# Wheelmod_rs485.net
KiCad netlist of a schematic drawn in EAGLE
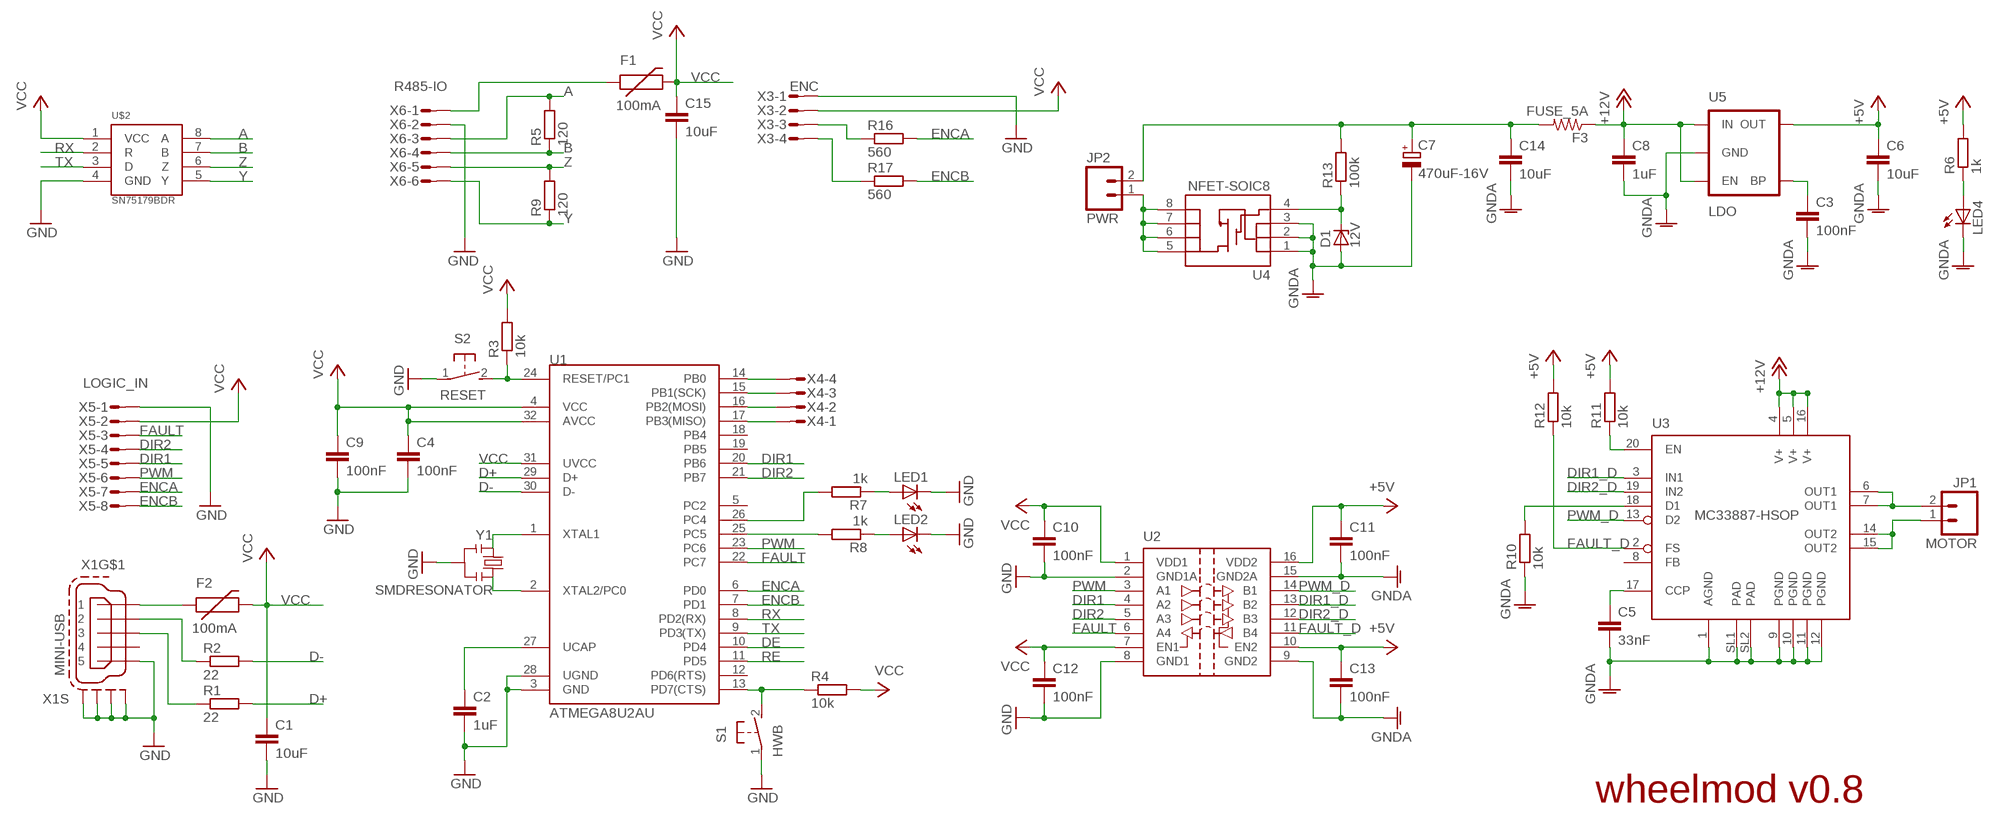
[diagram p0: schematic, sheet 1]

(export (version "E")
  (design (tool "Eeschema 10.0.6"))
  (components
    (comp (ref "C1")
      (value "10uF")
      (footprint "eagle-import:C1206K")
      (libsource (lib "eagle-import") (part "C-EUC1206K"))
    )
    (comp (ref "C2")
      (value "1uF")
      (footprint "eagle-import:C0603K")
      (libsource (lib "eagle-import") (part "C-EUC0603K"))
    )
    (comp (ref "C3")
      (value "100nF")
      (footprint "eagle-import:C0603K")
      (libsource (lib "eagle-import") (part "C-EUC0603K"))
    )
    (comp (ref "C4")
      (value "100nF")
      (footprint "eagle-import:C0603K")
      (libsource (lib "eagle-import") (part "C-EUC0603K"))
    )
    (comp (ref "C5")
      (value "33nF")
      (footprint "eagle-import:C0603K")
      (libsource (lib "eagle-import") (part "C-EUC0603K"))
    )
    (comp (ref "C6")
      (value "10uF")
      (footprint "eagle-import:C1206K")
      (libsource (lib "eagle-import") (part "C-EUC1206K"))
    )
    (comp (ref "C7")
      (value "470uF-16V")
      (footprint "eagle-import:E3,5-8")
      (libsource (lib "eagle-import") (part "CPOL-EUE3.5-8"))
    )
    (comp (ref "C8")
      (value "1uF")
      (footprint "eagle-import:C0603K")
      (libsource (lib "eagle-import") (part "C-EUC0603K"))
    )
    (comp (ref "C9")
      (value "100nF")
      (footprint "eagle-import:C0603K")
      (libsource (lib "eagle-import") (part "C-EUC0603K"))
    )
    (comp (ref "C10")
      (value "100nF")
      (footprint "eagle-import:C0603K")
      (libsource (lib "eagle-import") (part "C-EUC0603K"))
    )
    (comp (ref "C11")
      (value "100nF")
      (footprint "eagle-import:C0603K")
      (libsource (lib "eagle-import") (part "C-EUC0603K"))
    )
    (comp (ref "C12")
      (value "100nF")
      (footprint "eagle-import:C0603K")
      (libsource (lib "eagle-import") (part "C-EUC0603K"))
    )
    (comp (ref "C13")
      (value "100nF")
      (footprint "eagle-import:C0603K")
      (libsource (lib "eagle-import") (part "C-EUC0603K"))
    )
    (comp (ref "C14")
      (value "10uF")
      (footprint "eagle-import:C1206K")
      (libsource (lib "eagle-import") (part "C-EUC1206K"))
    )
    (comp (ref "C15")
      (value "10uF")
      (footprint "eagle-import:C1206K")
      (libsource (lib "eagle-import") (part "C-EUC1206K"))
    )
    (comp (ref "D1")
      (value "12V")
      (footprint "eagle-import:SOD123")
      (libsource (lib "eagle-import") (part "ZENER-DIODESOD123"))
    )
    (comp (ref "F1")
      (value "100mA")
      (footprint "eagle-import:PTC-1206")
      (libsource (lib "eagle-import") (part "PTCSMD"))
    )
    (comp (ref "F2")
      (value "100mA")
      (footprint "eagle-import:PTC-1206")
      (libsource (lib "eagle-import") (part "PTCSMD"))
    )
    (comp (ref "F3")
      (value "FUSE_5A")
      (footprint "eagle-import:R1206")
      (libsource (lib "eagle-import") (part "R-US_R1206"))
    )
    (comp (ref "JP1")
      (value "MOTOR")
      (footprint "eagle-import:SCREWTERMINAL-3.5MM-2")
      (libsource (lib "eagle-import") (part "M023.5MM"))
    )
    (comp (ref "JP2")
      (value "PWR")
      (footprint "eagle-import:SCREWTERMINAL-3.5MM-2")
      (libsource (lib "eagle-import") (part "M023.5MM"))
    )
    (comp (ref "LED1")
      (value "LEDCHIP-LED0603")
      (footprint "eagle-import:CHIP-LED0603")
      (libsource (lib "eagle-import") (part "LEDCHIP-LED0603"))
    )
    (comp (ref "LED2")
      (value "LEDCHIP-LED0603")
      (footprint "eagle-import:CHIP-LED0603")
      (libsource (lib "eagle-import") (part "LEDCHIP-LED0603"))
    )
    (comp (ref "LED4")
      (value "LEDCHIP-LED0603")
      (footprint "eagle-import:CHIP-LED0603")
      (libsource (lib "eagle-import") (part "LEDCHIP-LED0603"))
    )
    (comp (ref "R1")
      (value "22")
      (footprint "eagle-import:R0603")
      (libsource (lib "eagle-import") (part "R-EU_R0603"))
    )
    (comp (ref "R2")
      (value "22")
      (footprint "eagle-import:R0603")
      (libsource (lib "eagle-import") (part "R-EU_R0603"))
    )
    (comp (ref "R3")
      (value "10k")
      (footprint "eagle-import:R0603")
      (libsource (lib "eagle-import") (part "R-EU_R0603"))
    )
    (comp (ref "R4")
      (value "10k")
      (footprint "eagle-import:R0603")
      (libsource (lib "eagle-import") (part "R-EU_R0603"))
    )
    (comp (ref "R5")
      (value "120")
      (footprint "eagle-import:R0603")
      (libsource (lib "eagle-import") (part "R-EU_R0603"))
    )
    (comp (ref "R6")
      (value "1k")
      (footprint "eagle-import:R0603")
      (libsource (lib "eagle-import") (part "R-EU_R0603"))
    )
    (comp (ref "R7")
      (value "1k")
      (footprint "eagle-import:R0603")
      (libsource (lib "eagle-import") (part "R-EU_R0603"))
    )
    (comp (ref "R8")
      (value "1k")
      (footprint "eagle-import:R0603")
      (libsource (lib "eagle-import") (part "R-EU_R0603"))
    )
    (comp (ref "R9")
      (value "120")
      (footprint "eagle-import:R0603")
      (libsource (lib "eagle-import") (part "R-EU_R0603"))
    )
    (comp (ref "R10")
      (value "10k")
      (footprint "eagle-import:R0603")
      (libsource (lib "eagle-import") (part "R-EU_R0603"))
    )
    (comp (ref "R11")
      (value "10k")
      (footprint "eagle-import:R0603")
      (libsource (lib "eagle-import") (part "R-EU_R0603"))
    )
    (comp (ref "R12")
      (value "10k")
      (footprint "eagle-import:R0603")
      (libsource (lib "eagle-import") (part "R-EU_R0603"))
    )
    (comp (ref "R13")
      (value "100k")
      (footprint "eagle-import:R0603")
      (libsource (lib "eagle-import") (part "R-EU_R0603"))
    )
    (comp (ref "R16")
      (value "560")
      (footprint "eagle-import:R0603")
      (libsource (lib "eagle-import") (part "R-EU_R0603"))
    )
    (comp (ref "R17")
      (value "560")
      (footprint "eagle-import:R0603")
      (libsource (lib "eagle-import") (part "R-EU_R0603"))
    )
    (comp (ref "S1")
      (value "HWB")
      (footprint "eagle-import:ADTSM3")
      (libsource (lib "eagle-import") (part "ADTSM3"))
    )
    (comp (ref "S2")
      (value "RESET")
      (footprint "eagle-import:ADTSM3")
      (libsource (lib "eagle-import") (part "ADTSM3"))
    )
    (comp (ref "U$2")
      (value "SN75179BDR")
      (footprint "eagle-import:SOIC8")
      (libsource (lib "eagle-import") (part "SN75179BDR"))
    )
    (comp (ref "U1")
      (value "ATMEGA8U2AU")
      (footprint "eagle-import:TQFP32-08")
      (libsource (lib "eagle-import") (part "ATMEGA8U2AU"))
    )
    (comp (ref "U2")
      (value "SI8441IS1")
      (footprint "eagle-import:SO16")
      (libsource (lib "eagle-import") (part "SI8441IS1"))
    )
    (comp (ref "U3")
      (value "MC33887-HSOP")
      (footprint "eagle-import:HSOP")
      (libsource (lib "eagle-import") (part "MC33887-HSOP"))
    )
    (comp (ref "U4")
      (value "NFET-SOIC8")
      (footprint "eagle-import:SO08")
      (libsource (lib "eagle-import") (part "MOSFET-NCHANNEL-SOIC8"))
    )
    (comp (ref "U5")
      (value "LDO")
      (footprint "eagle-import:SOT23-5")
      (libsource (lib "eagle-import") (part "V_REG_LDOSMD"))
    )
    (comp (ref "X1")
      (value "MINI-USB")
      (footprint "eagle-import:32005-301")
      (libsource (lib "eagle-import") (part "MINI-USB-SCHIELD-32005-301"))
    )
    (comp (ref "X3")
      (value "ENC")
      (footprint "eagle-import:MICROMATCH-4")
      (fields (field (name "MPN") "7-215464-4"))
      (libsource (lib "eagle-import") (part "MICROMATCH-4"))
    )
    (comp (ref "X4")
      (value "MICROMATCH-4")
      (footprint "eagle-import:MICROMATCH-4")
      (fields (field (name "MPN") "7-215464-4"))
      (libsource (lib "eagle-import") (part "MICROMATCH-4"))
    )
    (comp (ref "X5")
      (value "LOGIC_IN")
      (footprint "eagle-import:MICROMATCH-8")
      (fields (field (name "MF") "FARNELL") (field (name "MPN") "7-215464-8"))
      (libsource (lib "eagle-import") (part "MICROMATCH-8"))
    )
    (comp (ref "X6")
      (value "R485-IO")
      (footprint "eagle-import:MICROMATCH-6")
      (fields (field (name "MPN") "7-215464-6"))
      (libsource (lib "eagle-import") (part "MICROMATCH-6"))
    )
    (comp (ref "Y1")
      (value "SMDRESONATOR")
      (footprint "eagle-import:PBRC-M")
      (libsource (lib "eagle-import") (part "SMDRESONATOR45X20"))
    )
  )
  (nets
    (net (code "1") (name "+5V") (class "Default")
      (node (ref "C11") (pin "1") (pinfunction "1_1") (pintype "passive"))
      (node (ref "C13") (pin "1") (pinfunction "1_1") (pintype "passive"))
      (node (ref "C6") (pin "1") (pinfunction "1_1") (pintype "passive"))
      (node (ref "R11") (pin "2") (pinfunction "2_2") (pintype "passive"))
      (node (ref "R12") (pin "2") (pinfunction "2_2") (pintype "passive"))
      (node (ref "R6") (pin "2") (pinfunction "2_2") (pintype "passive"))
      (node (ref "U2") (pin "10") (pinfunction "EN2_10") (pintype "input"))
      (node (ref "U2") (pin "16") (pinfunction "VDD2_16") (pintype "power_in"))
      (node (ref "U5") (pin "5") (pinfunction "OUT_5") (pintype "passive"))
    )
    (net (code "2") (name "+12V") (class "Default")
      (node (ref "C8") (pin "1") (pinfunction "1_1") (pintype "passive"))
      (node (ref "F3") (pin "1") (pinfunction "1_1") (pintype "passive"))
      (node (ref "U3") (pin "16") (pinfunction "V+_16") (pintype "power_in"))
      (node (ref "U3") (pin "4") (pinfunction "V+_4") (pintype "power_in"))
      (node (ref "U3") (pin "5") (pinfunction "V+_5") (pintype "power_in"))
      (node (ref "U5") (pin "1") (pinfunction "IN_1") (pintype "input"))
      (node (ref "U5") (pin "3") (pinfunction "EN_3") (pintype "input"))
    )
    (net (code "3") (name "/A") (class "Default")
      (node (ref "R5") (pin "2") (pinfunction "2_2") (pintype "passive"))
      (node (ref "U$2") (pin "8") (pinfunction "A_8") (pintype "bidirectional"))
      (node (ref "X6") (pin "3") (pinfunction "S_3") (pintype "passive"))
    )
    (net (code "4") (name "/B") (class "Default")
      (node (ref "R5") (pin "1") (pinfunction "1_1") (pintype "passive"))
      (node (ref "U$2") (pin "7") (pinfunction "B_7") (pintype "bidirectional"))
      (node (ref "X6") (pin "4") (pinfunction "S_4") (pintype "passive"))
    )
    (net (code "5") (name "/D+") (class "Default")
      (node (ref "R1") (pin "2") (pinfunction "2_2") (pintype "passive"))
      (node (ref "U1") (pin "29") (pinfunction "D+_29") (pintype "bidirectional"))
    )
    (net (code "6") (name "/D-") (class "Default")
      (node (ref "R2") (pin "2") (pinfunction "2_2") (pintype "passive"))
      (node (ref "U1") (pin "30") (pinfunction "D-_30") (pintype "bidirectional"))
    )
    (net (code "7") (name "/DE") (class "Default")
      (node (ref "U1") (pin "10") (pinfunction "PD4_10") (pintype "bidirectional"))
    )
    (net (code "8") (name "/DIR1") (class "Default")
      (node (ref "U1") (pin "20") (pinfunction "PB6_20") (pintype "bidirectional"))
      (node (ref "U2") (pin "4") (pinfunction "A2_4") (pintype "input"))
      (node (ref "X5") (pin "5") (pinfunction "S_5") (pintype "passive"))
    )
    (net (code "9") (name "/DIR1_D") (class "Default")
      (node (ref "U2") (pin "13") (pinfunction "B2_13") (pintype "output"))
      (node (ref "U3") (pin "3") (pinfunction "IN1_3") (pintype "input"))
    )
    (net (code "10") (name "/DIR2") (class "Default")
      (node (ref "U1") (pin "21") (pinfunction "PB7_21") (pintype "bidirectional"))
      (node (ref "U2") (pin "5") (pinfunction "A3_5") (pintype "input"))
      (node (ref "X5") (pin "4") (pinfunction "S_4") (pintype "passive"))
    )
    (net (code "11") (name "/DIR2_D") (class "Default")
      (node (ref "U2") (pin "12") (pinfunction "B3_12") (pintype "output"))
      (node (ref "U3") (pin "19") (pinfunction "IN2_19") (pintype "input"))
    )
    (net (code "12") (name "/ENCA") (class "Default")
      (node (ref "R16") (pin "2") (pinfunction "2_2") (pintype "passive"))
      (node (ref "U1") (pin "6") (pinfunction "PD0_6") (pintype "bidirectional"))
      (node (ref "X5") (pin "7") (pinfunction "S_7") (pintype "passive"))
    )
    (net (code "13") (name "/ENCB") (class "Default")
      (node (ref "R17") (pin "2") (pinfunction "2_2") (pintype "passive"))
      (node (ref "U1") (pin "7") (pinfunction "PD1_7") (pintype "bidirectional"))
      (node (ref "X5") (pin "8") (pinfunction "S_8") (pintype "passive"))
    )
    (net (code "14") (name "/FAULT") (class "Default")
      (node (ref "U1") (pin "22") (pinfunction "PC7_22") (pintype "bidirectional"))
      (node (ref "U2") (pin "6") (pinfunction "A4_6") (pintype "input"))
      (node (ref "X5") (pin "3") (pinfunction "S_3") (pintype "passive"))
    )
    (net (code "15") (name "/FAULT_D") (class "Default")
      (node (ref "R12") (pin "1") (pinfunction "1_1") (pintype "passive"))
      (node (ref "U2") (pin "11") (pinfunction "B4_11") (pintype "output"))
      (node (ref "U3") (pin "2") (pinfunction "FS_2") (pintype "open_collector"))
    )
    (net (code "16") (name "/PWM") (class "Default")
      (node (ref "U1") (pin "23") (pinfunction "PC6_23") (pintype "bidirectional"))
      (node (ref "U2") (pin "3") (pinfunction "A1_3") (pintype "input"))
      (node (ref "X5") (pin "6") (pinfunction "S_6") (pintype "passive"))
    )
    (net (code "17") (name "/PWM_D") (class "Default")
      (node (ref "U2") (pin "14") (pinfunction "B1_14") (pintype "output"))
      (node (ref "U3") (pin "13") (pinfunction "D2_13") (pintype "input"))
    )
    (net (code "18") (name "/RE") (class "Default")
      (node (ref "U1") (pin "11") (pinfunction "PD5_11") (pintype "bidirectional"))
    )
    (net (code "19") (name "/RX") (class "Default")
      (node (ref "U$2") (pin "2") (pinfunction "R_2") (pintype "bidirectional"))
      (node (ref "U1") (pin "8") (pinfunction "PD2(RX)_8") (pintype "bidirectional"))
    )
    (net (code "20") (name "/TX") (class "Default")
      (node (ref "U$2") (pin "3") (pinfunction "D_3") (pintype "bidirectional"))
      (node (ref "U1") (pin "9") (pinfunction "PD3(TX)_9") (pintype "bidirectional"))
    )
    (net (code "21") (name "/Y") (class "Default")
      (node (ref "R9") (pin "1") (pinfunction "1_1") (pintype "passive"))
      (node (ref "U$2") (pin "5") (pinfunction "Y_5") (pintype "bidirectional"))
      (node (ref "X6") (pin "6") (pinfunction "S_6") (pintype "passive"))
    )
    (net (code "22") (name "/Z") (class "Default")
      (node (ref "R9") (pin "2") (pinfunction "2_2") (pintype "passive"))
      (node (ref "U$2") (pin "6") (pinfunction "Z_6") (pintype "bidirectional"))
      (node (ref "X6") (pin "5") (pinfunction "S_5") (pintype "passive"))
    )
    (net (code "23") (name "GND") (class "Default")
      (node (ref "C1") (pin "2") (pinfunction "2_2") (pintype "passive"))
      (node (ref "C10") (pin "2") (pinfunction "2_2") (pintype "passive"))
      (node (ref "C12") (pin "2") (pinfunction "2_2") (pintype "passive"))
      (node (ref "C15") (pin "2") (pinfunction "2_2") (pintype "passive"))
      (node (ref "C2") (pin "2") (pinfunction "2_2") (pintype "passive"))
      (node (ref "C4") (pin "2") (pinfunction "2_2") (pintype "passive"))
      (node (ref "C9") (pin "2") (pinfunction "2_2") (pintype "passive"))
      (node (ref "LED1") (pin "C") (pinfunction "C_C") (pintype "passive"))
      (node (ref "LED2") (pin "C") (pinfunction "C_C") (pintype "passive"))
      (node (ref "S1") (pin "1") (pinfunction "1_1") (pintype "passive"))
      (node (ref "S2") (pin "1") (pinfunction "1_1") (pintype "passive"))
      (node (ref "U$2") (pin "4") (pinfunction "GND_4") (pintype "bidirectional"))
      (node (ref "U1") (pin "28") (pinfunction "UGND_28") (pintype "bidirectional"))
      (node (ref "U1") (pin "3") (pinfunction "GND_3") (pintype "bidirectional"))
      (node (ref "U2") (pin "2") (pinfunction "GND1A_2") (pintype "power_in"))
      (node (ref "U2") (pin "8") (pinfunction "GND1_8") (pintype "power_in"))
      (node (ref "X1") (pin "5") (pinfunction "5_5") (pintype "passive"))
      (node (ref "X1") (pin "M1") (pinfunction "S1_M1") (pintype "passive"))
      (node (ref "X1") (pin "M2") (pinfunction "S2_M2") (pintype "passive"))
      (node (ref "X1") (pin "M3") (pinfunction "S3_M3") (pintype "passive"))
      (node (ref "X1") (pin "M4") (pinfunction "S4_M4") (pintype "passive"))
      (node (ref "X3") (pin "1") (pinfunction "S_1") (pintype "passive"))
      (node (ref "X5") (pin "1") (pinfunction "S_1") (pintype "passive"))
      (node (ref "X6") (pin "2") (pinfunction "S_2") (pintype "passive"))
      (node (ref "Y1") (pin "2") (pinfunction "P$2_2") (pintype "power_in"))
    )
    (net (code "24") (name "GNDA") (class "Default")
      (node (ref "C11") (pin "2") (pinfunction "2_2") (pintype "passive"))
      (node (ref "C13") (pin "2") (pinfunction "2_2") (pintype "passive"))
      (node (ref "C14") (pin "2") (pinfunction "2_2") (pintype "passive"))
      (node (ref "C3") (pin "2") (pinfunction "2_2") (pintype "passive"))
      (node (ref "C5") (pin "2") (pinfunction "2_2") (pintype "passive"))
      (node (ref "C6") (pin "2") (pinfunction "2_2") (pintype "passive"))
      (node (ref "C7") (pin "-") (pinfunction "-_-") (pintype "passive"))
      (node (ref "C8") (pin "2") (pinfunction "2_2") (pintype "passive"))
      (node (ref "D1") (pin "A") (pinfunction "A_A") (pintype "passive"))
      (node (ref "LED4") (pin "C") (pinfunction "C_C") (pintype "passive"))
      (node (ref "R10") (pin "1") (pinfunction "1_1") (pintype "passive"))
      (node (ref "U2") (pin "15") (pinfunction "GND2A_15") (pintype "power_in"))
      (node (ref "U2") (pin "9") (pinfunction "GND2_9") (pintype "power_in"))
      (node (ref "U3") (pin "1") (pinfunction "AGND_1") (pintype "power_in"))
      (node (ref "U3") (pin "10") (pinfunction "PGND_10") (pintype "power_in"))
      (node (ref "U3") (pin "11") (pinfunction "PGND_11") (pintype "power_in"))
      (node (ref "U3") (pin "12") (pinfunction "PGND_12") (pintype "power_in"))
      (node (ref "U3") (pin "9") (pinfunction "PGND_9") (pintype "power_in"))
      (node (ref "U3") (pin "SL1") (pinfunction "PAD_SL1") (pintype "passive"))
      (node (ref "U3") (pin "SL2") (pinfunction "PAD_SL2") (pintype "passive"))
      (node (ref "U4") (pin "1") (pinfunction "S_1") (pintype "bidirectional"))
      (node (ref "U4") (pin "2") (pinfunction "S_2") (pintype "bidirectional"))
      (node (ref "U4") (pin "3") (pinfunction "S_3") (pintype "bidirectional"))
      (node (ref "U5") (pin "2") (pinfunction "GND_2") (pintype "input"))
    )
    (net (code "25") (name "Net-(C14-Pad1)") (class "Default")
      (node (ref "C14") (pin "1") (pinfunction "1_1") (pintype "passive"))
      (node (ref "C7") (pin "+") (pinfunction "+_+") (pintype "passive"))
      (node (ref "F3") (pin "2") (pinfunction "2_2") (pintype "passive"))
      (node (ref "JP2") (pin "2") (pinfunction "2_2") (pintype "passive"))
      (node (ref "R13") (pin "2") (pinfunction "2_2") (pintype "passive"))
    )
    (net (code "26") (name "Net-(F2-Pad1)") (class "Default")
      (node (ref "F2") (pin "1") (pinfunction "1_1") (pintype "bidirectional"))
      (node (ref "X1") (pin "1") (pinfunction "1_1") (pintype "passive"))
    )
    (net (code "27") (name "Net-(JP1-Pad1)") (class "Default")
      (node (ref "JP1") (pin "1") (pinfunction "1_1") (pintype "passive"))
      (node (ref "U3") (pin "14") (pinfunction "OUT2_14") (pintype "bidirectional"))
      (node (ref "U3") (pin "15") (pinfunction "OUT2_15") (pintype "bidirectional"))
    )
    (net (code "28") (name "Net-(JP1-Pad2)") (class "Default")
      (node (ref "JP1") (pin "2") (pinfunction "2_2") (pintype "passive"))
      (node (ref "U3") (pin "6") (pinfunction "OUT1_6") (pintype "bidirectional"))
      (node (ref "U3") (pin "7") (pinfunction "OUT1_7") (pintype "bidirectional"))
    )
    (net (code "29") (name "Net-(JP2-Pad1)") (class "Default")
      (node (ref "JP2") (pin "1") (pinfunction "1_1") (pintype "passive"))
      (node (ref "U4") (pin "5") (pinfunction "D_5") (pintype "bidirectional"))
      (node (ref "U4") (pin "6") (pinfunction "D_6") (pintype "bidirectional"))
      (node (ref "U4") (pin "7") (pinfunction "D_7") (pintype "bidirectional"))
      (node (ref "U4") (pin "8") (pinfunction "D_8") (pintype "bidirectional"))
    )
    (net (code "30") (name "Net-(LED1-PadA)") (class "Default")
      (node (ref "LED1") (pin "A") (pinfunction "A_A") (pintype "passive"))
      (node (ref "R7") (pin "1") (pinfunction "1_1") (pintype "passive"))
    )
    (net (code "31") (name "Net-(LED2-PadA)") (class "Default")
      (node (ref "LED2") (pin "A") (pinfunction "A_A") (pintype "passive"))
      (node (ref "R8") (pin "1") (pinfunction "1_1") (pintype "passive"))
    )
    (net (code "32") (name "Net-(LED4-PadA)") (class "Default")
      (node (ref "LED4") (pin "A") (pinfunction "A_A") (pintype "passive"))
      (node (ref "R6") (pin "1") (pinfunction "1_1") (pintype "passive"))
    )
    (net (code "33") (name "Net-(R1-Pad1)") (class "Default")
      (node (ref "R1") (pin "1") (pinfunction "1_1") (pintype "passive"))
      (node (ref "X1") (pin "3") (pinfunction "3_3") (pintype "passive"))
    )
    (net (code "34") (name "Net-(R2-Pad1)") (class "Default")
      (node (ref "R2") (pin "1") (pinfunction "1_1") (pintype "passive"))
      (node (ref "X1") (pin "2") (pinfunction "2_2") (pintype "passive"))
    )
    (net (code "35") (name "Net-(U1-PB0)") (class "Default")
      (node (ref "U1") (pin "14") (pinfunction "PB0_14") (pintype "bidirectional"))
      (node (ref "X4") (pin "4") (pinfunction "S_4") (pintype "passive"))
    )
    (net (code "36") (name "Net-(U1-PB1(SCK))") (class "Default")
      (node (ref "U1") (pin "15") (pinfunction "PB1(SCK)_15") (pintype "bidirectional"))
      (node (ref "X4") (pin "3") (pinfunction "S_3") (pintype "passive"))
    )
    (net (code "37") (name "Net-(U1-PB2(MOSI))") (class "Default")
      (node (ref "U1") (pin "16") (pinfunction "PB2(MOSI)_16") (pintype "bidirectional"))
      (node (ref "X4") (pin "2") (pinfunction "S_2") (pintype "passive"))
    )
    (net (code "38") (name "Net-(U1-PB3(MISO))") (class "Default")
      (node (ref "U1") (pin "17") (pinfunction "PB3(MISO)_17") (pintype "bidirectional"))
      (node (ref "X4") (pin "1") (pinfunction "S_1") (pintype "passive"))
    )
    (net (code "39") (name "Net-(U1-PC4)") (class "Default")
      (node (ref "R7") (pin "2") (pinfunction "2_2") (pintype "passive"))
      (node (ref "U1") (pin "26") (pinfunction "PC4_26") (pintype "bidirectional"))
    )
    (net (code "40") (name "Net-(U1-PC5)") (class "Default")
      (node (ref "R8") (pin "2") (pinfunction "2_2") (pintype "passive"))
      (node (ref "U1") (pin "25") (pinfunction "PC5_25") (pintype "bidirectional"))
    )
    (net (code "41") (name "Net-(U1-PD7(CTS))") (class "Default")
      (node (ref "R4") (pin "1") (pinfunction "1_1") (pintype "passive"))
      (node (ref "S1") (pin "2") (pinfunction "2_2") (pintype "passive"))
      (node (ref "U1") (pin "13") (pinfunction "PD7(CTS)_13") (pintype "bidirectional"))
    )
    (net (code "42") (name "Net-(U1-RESET{slash}PC1)") (class "Default")
      (node (ref "R3") (pin "1") (pinfunction "1_1") (pintype "passive"))
      (node (ref "S2") (pin "2") (pinfunction "2_2") (pintype "passive"))
      (node (ref "U1") (pin "24") (pinfunction "RESET/PC1_24") (pintype "bidirectional"))
    )
    (net (code "43") (name "Net-(U1-UCAP)") (class "Default")
      (node (ref "C2") (pin "1") (pinfunction "1_1") (pintype "passive"))
      (node (ref "U1") (pin "27") (pinfunction "UCAP_27") (pintype "bidirectional"))
    )
    (net (code "44") (name "Net-(U1-XTAL1)") (class "Default")
      (node (ref "U1") (pin "1") (pinfunction "XTAL1_1") (pintype "bidirectional"))
      (node (ref "Y1") (pin "1") (pinfunction "P$1_1") (pintype "bidirectional"))
    )
    (net (code "45") (name "Net-(U1-XTAL2{slash}PC0)") (class "Default")
      (node (ref "U1") (pin "2") (pinfunction "XTAL2/PC0_2") (pintype "bidirectional"))
      (node (ref "Y1") (pin "3") (pinfunction "P$3_3") (pintype "bidirectional"))
    )
    (net (code "46") (name "Net-(U3-CCP)") (class "Default")
      (node (ref "C5") (pin "1") (pinfunction "1_1") (pintype "passive"))
      (node (ref "U3") (pin "17") (pinfunction "CCP_17") (pintype "passive"))
    )
    (net (code "47") (name "Net-(U3-D1)") (class "Default")
      (node (ref "R10") (pin "2") (pinfunction "2_2") (pintype "passive"))
      (node (ref "U3") (pin "18") (pinfunction "D1_18") (pintype "input"))
    )
    (net (code "48") (name "Net-(U3-EN)") (class "Default")
      (node (ref "R11") (pin "1") (pinfunction "1_1") (pintype "passive"))
      (node (ref "U3") (pin "20") (pinfunction "EN_20") (pintype "input"))
    )
    (net (code "49") (name "Net-(U4-G)") (class "Default")
      (node (ref "D1") (pin "C") (pinfunction "C_C") (pintype "passive"))
      (node (ref "R13") (pin "1") (pinfunction "1_1") (pintype "passive"))
      (node (ref "U4") (pin "4") (pinfunction "G_4") (pintype "bidirectional"))
    )
    (net (code "50") (name "Net-(U5-BP)") (class "Default")
      (node (ref "C3") (pin "1") (pinfunction "1_1") (pintype "passive"))
      (node (ref "U5") (pin "4") (pinfunction "BP_4") (pintype "input"))
    )
    (net (code "51") (name "Net-(X3C-S)") (class "Default")
      (node (ref "R16") (pin "1") (pinfunction "1_1") (pintype "passive"))
      (node (ref "X3") (pin "3") (pinfunction "S_3") (pintype "passive"))
    )
    (net (code "52") (name "Net-(X3D-S)") (class "Default")
      (node (ref "R17") (pin "1") (pinfunction "1_1") (pintype "passive"))
      (node (ref "X3") (pin "4") (pinfunction "S_4") (pintype "passive"))
    )
    (net (code "53") (name "Net-(X6A-S)") (class "Default")
      (node (ref "F1") (pin "1") (pinfunction "1_1") (pintype "bidirectional"))
      (node (ref "X6") (pin "1") (pinfunction "S_1") (pintype "passive"))
    )
    (net (code "54") (name "VCC") (class "Default")
      (node (ref "C1") (pin "1") (pinfunction "1_1") (pintype "passive"))
      (node (ref "C10") (pin "1") (pinfunction "1_1") (pintype "passive"))
      (node (ref "C12") (pin "1") (pinfunction "1_1") (pintype "passive"))
      (node (ref "C15") (pin "1") (pinfunction "1_1") (pintype "passive"))
      (node (ref "C4") (pin "1") (pinfunction "1_1") (pintype "passive"))
      (node (ref "C9") (pin "1") (pinfunction "1_1") (pintype "passive"))
      (node (ref "F1") (pin "2") (pinfunction "2_2") (pintype "bidirectional"))
      (node (ref "F2") (pin "2") (pinfunction "2_2") (pintype "bidirectional"))
      (node (ref "R3") (pin "2") (pinfunction "2_2") (pintype "passive"))
      (node (ref "R4") (pin "2") (pinfunction "2_2") (pintype "passive"))
      (node (ref "U$2") (pin "1") (pinfunction "VCC_1") (pintype "bidirectional"))
      (node (ref "U1") (pin "31") (pinfunction "UVCC_31") (pintype "bidirectional"))
      (node (ref "U1") (pin "32") (pinfunction "AVCC_32") (pintype "bidirectional"))
      (node (ref "U1") (pin "4") (pinfunction "VCC_4") (pintype "bidirectional"))
      (node (ref "U2") (pin "1") (pinfunction "VDD1_1") (pintype "power_in"))
      (node (ref "U2") (pin "7") (pinfunction "EN1_7") (pintype "input"))
      (node (ref "X3") (pin "2") (pinfunction "S_2") (pintype "passive"))
      (node (ref "X5") (pin "2") (pinfunction "S_2") (pintype "passive"))
    )
    (net (code "55") (name "unconnected-(U1-PB4-Pad18)") (class "Default")
      (node (ref "U1") (pin "18") (pinfunction "PB4_18") (pintype "bidirectional"))
    )
    (net (code "56") (name "unconnected-(U1-PB5-Pad19)") (class "Default")
      (node (ref "U1") (pin "19") (pinfunction "PB5_19") (pintype "bidirectional"))
    )
    (net (code "57") (name "unconnected-(U1-PC2-Pad5)") (class "Default")
      (node (ref "U1") (pin "5") (pinfunction "PC2_5") (pintype "bidirectional"))
    )
    (net (code "58") (name "unconnected-(U1-PD6(RTS)-Pad12)") (class "Default")
      (node (ref "U1") (pin "12") (pinfunction "PD6(RTS)_12") (pintype "bidirectional"))
    )
    (net (code "59") (name "unconnected-(U3-FB-Pad8)") (class "Default")
      (node (ref "U3") (pin "8") (pinfunction "FB_8") (pintype "output"))
    )
    (net (code "60") (name "unconnected-(X1-Pad4)") (class "Default")
      (node (ref "X1") (pin "4") (pinfunction "4_4") (pintype "passive"))
    )
  )
)
